# Vesta_cape_wifi.net
KiCad netlist of a schematic drawn in Altium Designer
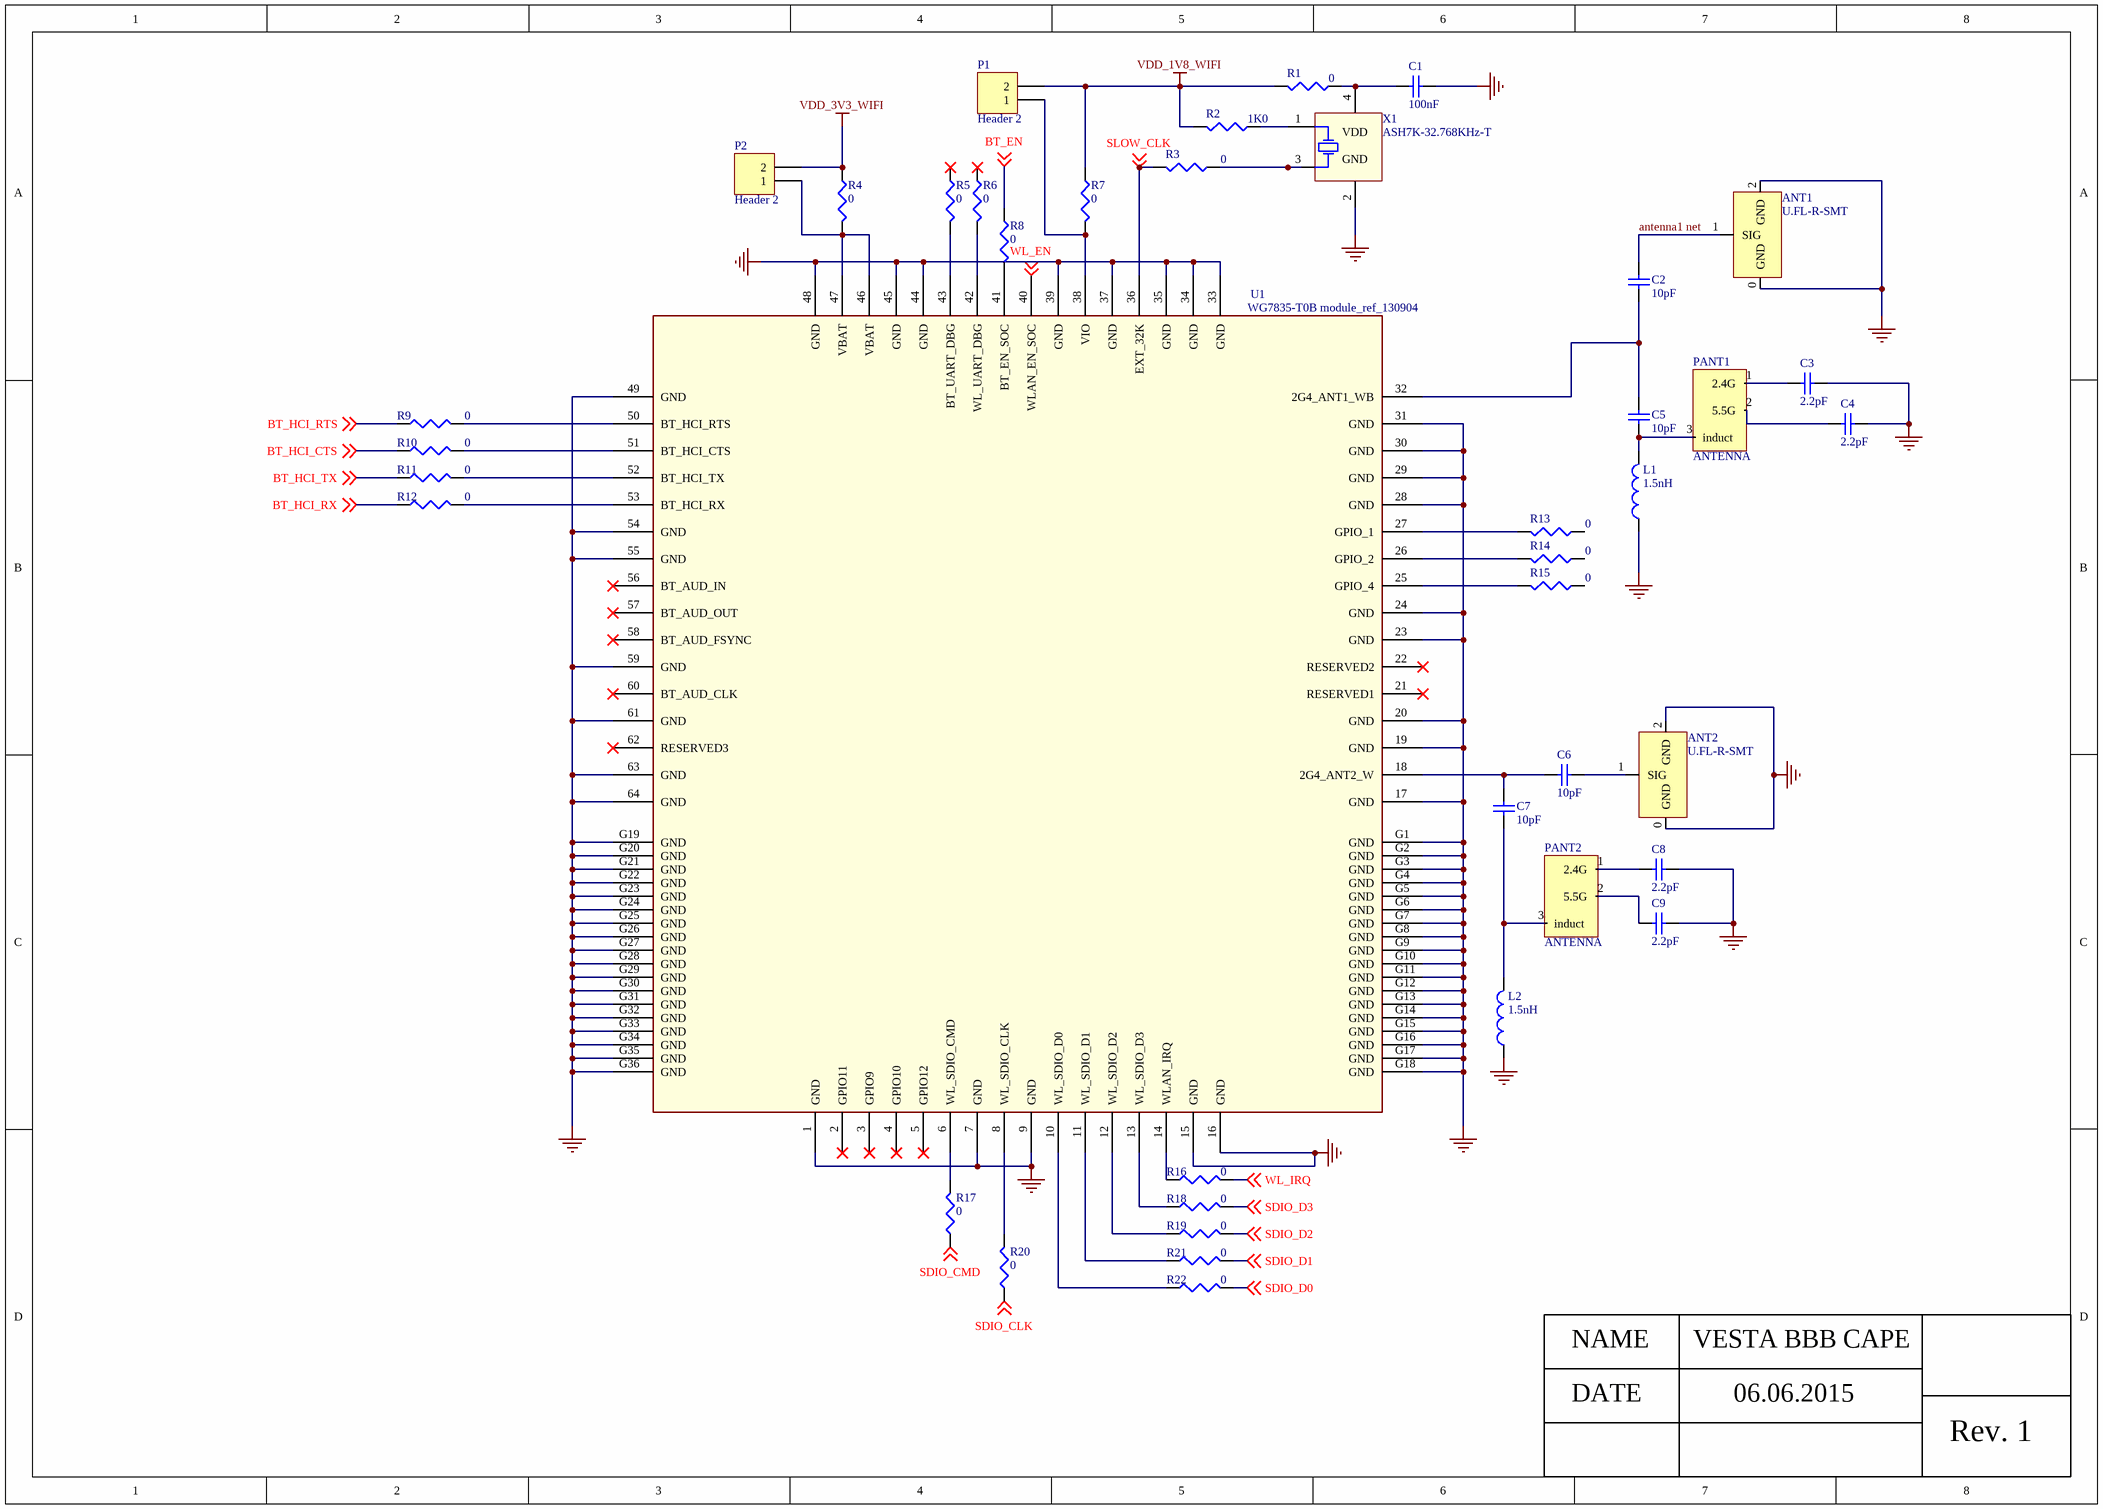
[diagram p0: Vesta_cape_wifi.SchDoc]

(export (version "E")
  (design (tool "Eeschema 10.0.6"))
  (components
    (comp (ref "ANT1")
      (value "U.FL-R-SMT")
      (footprint "U.FL-R-SMT")
      (libsource (lib "Vesta_cape") (part "U.FL-R-SMT"))
    )
    (comp (ref "ANT2")
      (value "U.FL-R-SMT")
      (footprint "U.FL-R-SMT")
      (libsource (lib "Vesta_cape") (part "U.FL-R-SMT"))
    )
    (comp (ref "C1")
      (value "100nF")
      (footprint "C1206")
      (description "Capacitor (Semiconductor SIM Model)")
      (fields (field (name "PUBLISHER") "Altium Limited"))
      (libsource (lib "Miscellaneous Devices") (part "Cap Semi"))
    )
    (comp (ref "C2")
      (value "10pF")
      (footprint "Capacitor_0603")
      (description "Capacitor (Semiconductor SIM Model)")
      (fields (field (name "PUBLISHER") "Altium Limited"))
      (libsource (lib "Miscellaneous Devices") (part "Cap Semi"))
    )
    (comp (ref "C3")
      (value "2.2pF")
      (footprint "Capacitor_0603")
      (description "Capacitor (Semiconductor SIM Model)")
      (fields (field (name "PUBLISHER") "Altium Limited"))
      (libsource (lib "Miscellaneous Devices") (part "Cap Semi"))
    )
    (comp (ref "C4")
      (value "2.2pF")
      (footprint "Capacitor_0603")
      (description "Capacitor (Semiconductor SIM Model)")
      (fields (field (name "PUBLISHER") "Altium Limited"))
      (libsource (lib "Miscellaneous Devices") (part "Cap Semi"))
    )
    (comp (ref "C5")
      (value "10pF")
      (footprint "Capacitor_0603")
      (description "Capacitor (Semiconductor SIM Model)")
      (fields (field (name "PUBLISHER") "Altium Limited"))
      (libsource (lib "Miscellaneous Devices") (part "Cap Semi"))
    )
    (comp (ref "C6")
      (value "10pF")
      (footprint "Capacitor_0603")
      (description "Capacitor (Semiconductor SIM Model)")
      (fields (field (name "PUBLISHER") "Altium Limited"))
      (libsource (lib "Miscellaneous Devices") (part "Cap Semi"))
    )
    (comp (ref "C7")
      (value "10pF")
      (footprint "Capacitor_0603")
      (description "Capacitor (Semiconductor SIM Model)")
      (fields (field (name "PUBLISHER") "Altium Limited"))
      (libsource (lib "Miscellaneous Devices") (part "Cap Semi"))
    )
    (comp (ref "C8")
      (value "2.2pF")
      (footprint "Capacitor_0603")
      (description "Capacitor (Semiconductor SIM Model)")
      (fields (field (name "PUBLISHER") "Altium Limited"))
      (libsource (lib "Miscellaneous Devices") (part "Cap Semi"))
    )
    (comp (ref "C9")
      (value "2.2pF")
      (footprint "Capacitor_0603")
      (description "Capacitor (Semiconductor SIM Model)")
      (fields (field (name "PUBLISHER") "Altium Limited"))
      (libsource (lib "Miscellaneous Devices") (part "Cap Semi"))
    )
    (comp (ref "L1")
      (value "1.5nH")
      (footprint "0402-A")
      (description "Inductor")
      (fields (field (name "PUBLISHER") "Altium Limited"))
      (libsource (lib "Miscellaneous Devices") (part "Inductor"))
    )
    (comp (ref "L2")
      (value "1.5nH")
      (footprint "0402-A")
      (description "Inductor")
      (fields (field (name "PUBLISHER") "Altium Limited"))
      (libsource (lib "Miscellaneous Devices") (part "Inductor"))
    )
    (comp (ref "P1")
      (value "Header 2")
      (footprint "HDR1X2")
      (description "Header, 2-Pin")
      (fields (field (name "PUBLISHER") "Altium Limited"))
      (libsource (lib "Miscellaneous Connectors") (part "Header 2"))
    )
    (comp (ref "P2")
      (value "Header 2")
      (footprint "HDR1X2")
      (description "Header, 2-Pin")
      (fields (field (name "PUBLISHER") "Altium Limited"))
      (libsource (lib "Miscellaneous Connectors") (part "Header 2"))
    )
    (comp (ref "PANT1")
      (value "ANTENNA")
      (footprint "ANT_BRD_CUT")
      (libsource (lib "Vesta_cape") (part "ANTENNA"))
    )
    (comp (ref "PANT2")
      (value "ANTENNA")
      (footprint "ANT_BRD_CUT")
      (libsource (lib "Vesta_cape") (part "ANTENNA"))
    )
    (comp (ref "R1")
      (value "0")
      (footprint "J1-0603")
      (description "Resistor")
      (fields (field (name "PUBLISHER") "Altium Limited"))
      (libsource (lib "Miscellaneous Devices") (part "Res3"))
    )
    (comp (ref "R2")
      (value "1K0")
      (footprint "J1-0603")
      (description "Resistor")
      (fields (field (name "PUBLISHER") "Altium Limited"))
      (libsource (lib "Miscellaneous Devices") (part "Res3"))
    )
    (comp (ref "R3")
      (value "0")
      (footprint "J1-0603")
      (description "Resistor")
      (fields (field (name "PUBLISHER") "Altium Limited"))
      (libsource (lib "Miscellaneous Devices") (part "Res3"))
    )
    (comp (ref "R4")
      (value "0")
      (footprint "J1-0603")
      (description "Resistor")
      (fields (field (name "PUBLISHER") "Altium Limited"))
      (libsource (lib "Miscellaneous Devices") (part "Res3"))
    )
    (comp (ref "R5")
      (value "0")
      (footprint "J1-0603")
      (description "Resistor")
      (fields (field (name "PUBLISHER") "Altium Limited"))
      (libsource (lib "Miscellaneous Devices") (part "Res3"))
    )
    (comp (ref "R6")
      (value "0")
      (footprint "J1-0603")
      (description "Resistor")
      (fields (field (name "PUBLISHER") "Altium Limited"))
      (libsource (lib "Miscellaneous Devices") (part "Res3"))
    )
    (comp (ref "R7")
      (value "0")
      (footprint "J1-0603")
      (description "Resistor")
      (fields (field (name "PUBLISHER") "Altium Limited"))
      (libsource (lib "Miscellaneous Devices") (part "Res3"))
    )
    (comp (ref "R8")
      (value "0")
      (footprint "J1-0603")
      (description "Resistor")
      (fields (field (name "PUBLISHER") "Altium Limited"))
      (libsource (lib "Miscellaneous Devices") (part "Res3"))
    )
    (comp (ref "R9")
      (value "0")
      (footprint "J1-0603")
      (description "Resistor")
      (fields (field (name "PUBLISHER") "Altium Limited"))
      (libsource (lib "Miscellaneous Devices") (part "Res3"))
    )
    (comp (ref "R10")
      (value "0")
      (footprint "J1-0603")
      (description "Resistor")
      (fields (field (name "PUBLISHER") "Altium Limited"))
      (libsource (lib "Miscellaneous Devices") (part "Res3"))
    )
    (comp (ref "R11")
      (value "0")
      (footprint "J1-0603")
      (description "Resistor")
      (fields (field (name "PUBLISHER") "Altium Limited"))
      (libsource (lib "Miscellaneous Devices") (part "Res3"))
    )
    (comp (ref "R12")
      (value "0")
      (footprint "J1-0603")
      (description "Resistor")
      (fields (field (name "PUBLISHER") "Altium Limited"))
      (libsource (lib "Miscellaneous Devices") (part "Res3"))
    )
    (comp (ref "R13")
      (value "0")
      (footprint "J1-0603")
      (description "Resistor")
      (fields (field (name "PUBLISHER") "Altium Limited"))
      (libsource (lib "Miscellaneous Devices") (part "Res3"))
    )
    (comp (ref "R14")
      (value "0")
      (footprint "J1-0603")
      (description "Resistor")
      (fields (field (name "PUBLISHER") "Altium Limited"))
      (libsource (lib "Miscellaneous Devices") (part "Res3"))
    )
    (comp (ref "R15")
      (value "0")
      (footprint "J1-0603")
      (description "Resistor")
      (fields (field (name "PUBLISHER") "Altium Limited"))
      (libsource (lib "Miscellaneous Devices") (part "Res3"))
    )
    (comp (ref "R16")
      (value "0")
      (footprint "J1-0603")
      (description "Resistor")
      (fields (field (name "PUBLISHER") "Altium Limited"))
      (libsource (lib "Miscellaneous Devices") (part "Res3"))
    )
    (comp (ref "R17")
      (value "0")
      (footprint "J1-0603")
      (description "Resistor")
      (fields (field (name "PUBLISHER") "Altium Limited"))
      (libsource (lib "Miscellaneous Devices") (part "Res3"))
    )
    (comp (ref "R18")
      (value "0")
      (footprint "J1-0603")
      (description "Resistor")
      (fields (field (name "PUBLISHER") "Altium Limited"))
      (libsource (lib "Miscellaneous Devices") (part "Res3"))
    )
    (comp (ref "R19")
      (value "0")
      (footprint "J1-0603")
      (description "Resistor")
      (fields (field (name "PUBLISHER") "Altium Limited"))
      (libsource (lib "Miscellaneous Devices") (part "Res3"))
    )
    (comp (ref "R20")
      (value "0")
      (footprint "J1-0603")
      (description "Resistor")
      (fields (field (name "PUBLISHER") "Altium Limited"))
      (libsource (lib "Miscellaneous Devices") (part "Res3"))
    )
    (comp (ref "R21")
      (value "0")
      (footprint "J1-0603")
      (description "Resistor")
      (fields (field (name "PUBLISHER") "Altium Limited"))
      (libsource (lib "Miscellaneous Devices") (part "Res3"))
    )
    (comp (ref "R22")
      (value "0")
      (footprint "J1-0603")
      (description "Resistor")
      (fields (field (name "PUBLISHER") "Altium Limited"))
      (libsource (lib "Miscellaneous Devices") (part "Res3"))
    )
    (comp (ref "U1")
      (value "WG7835-T0B module_ref_130904")
      (footprint "E-13.4X13.3-N100_0.75-TOP")
      (libsource (lib "WL1835MODCOM8B_Library") (part "WG7835-T0B module_ref_130904"))
    )
    (comp (ref "X1")
      (value "ASH7K-32.768KHz-T")
      (footprint "ABRA-ASH7K-4_V")
      (description "Crystal Oscillator, 32.768 kHz, -40 to 80 degC, 3.2 x 1.5 x 1.0 mm SMD, Tape and Reel")
      (fields (field (name "MANUFACTURER") "Abracon"))
      (libsource (lib "Altium Content Vault") (part "CMP-0448-00001-2"))
    )
  )
  (nets
    (net (code "1") (name "/antenna1 net") (class "Default")
      (node (ref "ANT1") (pin "1") (pinfunction "SIG_1") (pintype "passive"))
      (node (ref "C2") (pin "2") (pinfunction "2_2") (pintype "passive"))
    )
    (net (code "2") (name "BT_EN") (class "Default")
      (node (ref "R8") (pin "1") (pinfunction "1_1") (pintype "passive"))
    )
    (net (code "3") (name "BT_HCI_CTS") (class "Default")
      (node (ref "R10") (pin "1") (pinfunction "1_1") (pintype "passive"))
    )
    (net (code "4") (name "BT_HCI_RTS") (class "Default")
      (node (ref "R9") (pin "1") (pinfunction "1_1") (pintype "passive"))
    )
    (net (code "5") (name "BT_HCI_RX") (class "Default")
      (node (ref "R12") (pin "1") (pinfunction "1_1") (pintype "passive"))
    )
    (net (code "6") (name "BT_HCI_TX") (class "Default")
      (node (ref "R11") (pin "1") (pinfunction "1_1") (pintype "passive"))
    )
    (net (code "7") (name "GND") (class "Default")
      (node (ref "ANT1") (pin "0") (pinfunction "GND_0") (pintype "passive"))
      (node (ref "ANT1") (pin "2") (pinfunction "GND_2") (pintype "passive"))
      (node (ref "ANT2") (pin "0") (pinfunction "GND_0") (pintype "passive"))
      (node (ref "ANT2") (pin "2") (pinfunction "GND_2") (pintype "passive"))
      (node (ref "C1") (pin "1") (pinfunction "1_1") (pintype "passive"))
      (node (ref "C3") (pin "2") (pinfunction "2_2") (pintype "passive"))
      (node (ref "C4") (pin "2") (pinfunction "2_2") (pintype "passive"))
      (node (ref "C8") (pin "2") (pinfunction "2_2") (pintype "passive"))
      (node (ref "C9") (pin "2") (pinfunction "2_2") (pintype "passive"))
      (node (ref "L1") (pin "1") (pinfunction "1_1") (pintype "passive"))
      (node (ref "L2") (pin "1") (pinfunction "1_1") (pintype "passive"))
      (node (ref "U1") (pin "1") (pinfunction "GND_1") (pintype "power_in"))
      (node (ref "U1") (pin "15") (pinfunction "GND_15") (pintype "power_in"))
      (node (ref "U1") (pin "16") (pinfunction "GND_16") (pintype "power_in"))
      (node (ref "U1") (pin "17") (pinfunction "GND_17") (pintype "power_in"))
      (node (ref "U1") (pin "19") (pinfunction "GND_19") (pintype "power_in"))
      (node (ref "U1") (pin "20") (pinfunction "GND_20") (pintype "power_in"))
      (node (ref "U1") (pin "23") (pinfunction "GND_23") (pintype "power_in"))
      (node (ref "U1") (pin "24") (pinfunction "GND_24") (pintype "power_in"))
      (node (ref "U1") (pin "28") (pinfunction "GND_28") (pintype "power_in"))
      (node (ref "U1") (pin "29") (pinfunction "GND_29") (pintype "power_in"))
      (node (ref "U1") (pin "30") (pinfunction "GND_30") (pintype "power_in"))
      (node (ref "U1") (pin "31") (pinfunction "GND_31") (pintype "power_in"))
      (node (ref "U1") (pin "33") (pinfunction "GND_33") (pintype "power_in"))
      (node (ref "U1") (pin "34") (pinfunction "GND_34") (pintype "power_in"))
      (node (ref "U1") (pin "35") (pinfunction "GND_35") (pintype "power_in"))
      (node (ref "U1") (pin "37") (pinfunction "GND_37") (pintype "power_in"))
      (node (ref "U1") (pin "39") (pinfunction "GND_39") (pintype "power_in"))
      (node (ref "U1") (pin "44") (pinfunction "GND_44") (pintype "power_in"))
      (node (ref "U1") (pin "45") (pinfunction "GND_45") (pintype "power_in"))
      (node (ref "U1") (pin "48") (pinfunction "GND_48") (pintype "power_in"))
      (node (ref "U1") (pin "49") (pinfunction "GND_49") (pintype "power_in"))
      (node (ref "U1") (pin "54") (pinfunction "GND_54") (pintype "power_in"))
      (node (ref "U1") (pin "55") (pinfunction "GND_55") (pintype "power_in"))
      (node (ref "U1") (pin "59") (pinfunction "GND_59") (pintype "power_in"))
      (node (ref "U1") (pin "61") (pinfunction "GND_61") (pintype "power_in"))
      (node (ref "U1") (pin "63") (pinfunction "GND_63") (pintype "power_in"))
      (node (ref "U1") (pin "64") (pinfunction "GND_64") (pintype "power_in"))
      (node (ref "U1") (pin "7") (pinfunction "GND_7") (pintype "power_in"))
      (node (ref "U1") (pin "9") (pinfunction "GND_9") (pintype "power_in"))
      (node (ref "U1") (pin "G1") (pinfunction "GND_G1") (pintype "power_in"))
      (node (ref "U1") (pin "G10") (pinfunction "GND_G10") (pintype "power_in"))
      (node (ref "U1") (pin "G11") (pinfunction "GND_G11") (pintype "power_in"))
      (node (ref "U1") (pin "G12") (pinfunction "GND_G12") (pintype "power_in"))
      (node (ref "U1") (pin "G13") (pinfunction "GND_G13") (pintype "power_in"))
      (node (ref "U1") (pin "G14") (pinfunction "GND_G14") (pintype "power_in"))
      (node (ref "U1") (pin "G15") (pinfunction "GND_G15") (pintype "power_in"))
      (node (ref "U1") (pin "G16") (pinfunction "GND_G16") (pintype "power_in"))
      (node (ref "U1") (pin "G17") (pinfunction "GND_G17") (pintype "power_in"))
      (node (ref "U1") (pin "G18") (pinfunction "GND_G18") (pintype "power_in"))
      (node (ref "U1") (pin "G19") (pinfunction "GND_G19") (pintype "power_in"))
      (node (ref "U1") (pin "G2") (pinfunction "GND_G2") (pintype "power_in"))
      (node (ref "U1") (pin "G20") (pinfunction "GND_G20") (pintype "power_in"))
      (node (ref "U1") (pin "G21") (pinfunction "GND_G21") (pintype "power_in"))
      (node (ref "U1") (pin "G22") (pinfunction "GND_G22") (pintype "power_in"))
      (node (ref "U1") (pin "G23") (pinfunction "GND_G23") (pintype "power_in"))
      (node (ref "U1") (pin "G24") (pinfunction "GND_G24") (pintype "power_in"))
      (node (ref "U1") (pin "G25") (pinfunction "GND_G25") (pintype "power_in"))
      (node (ref "U1") (pin "G26") (pinfunction "GND_G26") (pintype "power_in"))
      (node (ref "U1") (pin "G27") (pinfunction "GND_G27") (pintype "power_in"))
      (node (ref "U1") (pin "G28") (pinfunction "GND_G28") (pintype "power_in"))
      (node (ref "U1") (pin "G29") (pinfunction "GND_G29") (pintype "power_in"))
      (node (ref "U1") (pin "G3") (pinfunction "GND_G3") (pintype "power_in"))
      (node (ref "U1") (pin "G30") (pinfunction "GND_G30") (pintype "power_in"))
      (node (ref "U1") (pin "G31") (pinfunction "GND_G31") (pintype "power_in"))
      (node (ref "U1") (pin "G32") (pinfunction "GND_G32") (pintype "power_in"))
      (node (ref "U1") (pin "G33") (pinfunction "GND_G33") (pintype "power_in"))
      (node (ref "U1") (pin "G34") (pinfunction "GND_G34") (pintype "power_in"))
      (node (ref "U1") (pin "G35") (pinfunction "GND_G35") (pintype "power_in"))
      (node (ref "U1") (pin "G36") (pinfunction "GND_G36") (pintype "power_in"))
      (node (ref "U1") (pin "G4") (pinfunction "GND_G4") (pintype "power_in"))
      (node (ref "U1") (pin "G5") (pinfunction "GND_G5") (pintype "power_in"))
      (node (ref "U1") (pin "G6") (pinfunction "GND_G6") (pintype "power_in"))
      (node (ref "U1") (pin "G7") (pinfunction "GND_G7") (pintype "power_in"))
      (node (ref "U1") (pin "G8") (pinfunction "GND_G8") (pintype "power_in"))
      (node (ref "U1") (pin "G9") (pinfunction "GND_G9") (pintype "power_in"))
      (node (ref "X1") (pin "2") (pinfunction "GND_2") (pintype "power_in"))
    )
    (net (code "8") (name "Net-(ANT2-SIG)") (class "Default")
      (node (ref "ANT2") (pin "1") (pinfunction "SIG_1") (pintype "passive"))
      (node (ref "C6") (pin "2") (pinfunction "2_2") (pintype "passive"))
    )
    (net (code "9") (name "Net-(P2-Pad1)") (class "Default")
      (node (ref "P2") (pin "1") (pinfunction "1_1") (pintype "passive"))
      (node (ref "R4") (pin "2") (pinfunction "2_2") (pintype "passive"))
      (node (ref "U1") (pin "46") (pinfunction "VBAT_46") (pintype "power_in"))
      (node (ref "U1") (pin "47") (pinfunction "VBAT_47") (pintype "power_in"))
    )
    (net (code "10") (name "Net-(PANT1-2.4G)") (class "Default")
      (node (ref "C3") (pin "1") (pinfunction "1_1") (pintype "passive"))
      (node (ref "PANT1") (pin "1") (pinfunction "2.4G_1") (pintype "passive"))
    )
    (net (code "11") (name "Net-(PANT1-5.5G)") (class "Default")
      (node (ref "C4") (pin "1") (pinfunction "1_1") (pintype "passive"))
      (node (ref "PANT1") (pin "2") (pinfunction "5.5G_2") (pintype "passive"))
    )
    (net (code "12") (name "Net-(PANT1-induct)") (class "Default")
      (node (ref "C5") (pin "1") (pinfunction "1_1") (pintype "passive"))
      (node (ref "L1") (pin "2") (pinfunction "2_2") (pintype "passive"))
      (node (ref "PANT1") (pin "3") (pinfunction "induct_3") (pintype "passive"))
    )
    (net (code "13") (name "Net-(PANT2-2.4G)") (class "Default")
      (node (ref "C8") (pin "1") (pinfunction "1_1") (pintype "passive"))
      (node (ref "PANT2") (pin "1") (pinfunction "2.4G_1") (pintype "passive"))
    )
    (net (code "14") (name "Net-(PANT2-5.5G)") (class "Default")
      (node (ref "C9") (pin "1") (pinfunction "1_1") (pintype "passive"))
      (node (ref "PANT2") (pin "2") (pinfunction "5.5G_2") (pintype "passive"))
    )
    (net (code "15") (name "Net-(PANT2-induct)") (class "Default")
      (node (ref "C7") (pin "1") (pinfunction "1_1") (pintype "passive"))
      (node (ref "L2") (pin "2") (pinfunction "2_2") (pintype "passive"))
      (node (ref "PANT2") (pin "3") (pinfunction "induct_3") (pintype "passive"))
    )
    (net (code "16") (name "Net-(U1-2G4_ANT1_WB)") (class "Default")
      (node (ref "C2") (pin "1") (pinfunction "1_1") (pintype "passive"))
      (node (ref "C5") (pin "2") (pinfunction "2_2") (pintype "passive"))
      (node (ref "U1") (pin "32") (pinfunction "2G4_ANT1_WB_32") (pintype "passive"))
    )
    (net (code "17") (name "Net-(U1-2G4_ANT2_W)") (class "Default")
      (node (ref "C6") (pin "1") (pinfunction "1_1") (pintype "passive"))
      (node (ref "C7") (pin "2") (pinfunction "2_2") (pintype "passive"))
      (node (ref "U1") (pin "18") (pinfunction "2G4_ANT2_W_18") (pintype "passive"))
    )
    (net (code "18") (name "Net-(U1-BT_EN_SOC)") (class "Default")
      (node (ref "R8") (pin "2") (pinfunction "2_2") (pintype "passive"))
      (node (ref "U1") (pin "41") (pinfunction "BT_EN_SOC_41") (pintype "passive"))
    )
    (net (code "19") (name "Net-(U1-BT_HCI_CTS)") (class "Default")
      (node (ref "R10") (pin "2") (pinfunction "2_2") (pintype "passive"))
      (node (ref "U1") (pin "51") (pinfunction "BT_HCI_CTS_51") (pintype "passive"))
    )
    (net (code "20") (name "Net-(U1-BT_HCI_RTS)") (class "Default")
      (node (ref "R9") (pin "2") (pinfunction "2_2") (pintype "passive"))
      (node (ref "U1") (pin "50") (pinfunction "BT_HCI_RTS_50") (pintype "passive"))
    )
    (net (code "21") (name "Net-(U1-BT_HCI_RX)") (class "Default")
      (node (ref "R12") (pin "2") (pinfunction "2_2") (pintype "passive"))
      (node (ref "U1") (pin "53") (pinfunction "BT_HCI_RX_53") (pintype "passive"))
    )
    (net (code "22") (name "Net-(U1-BT_HCI_TX)") (class "Default")
      (node (ref "R11") (pin "2") (pinfunction "2_2") (pintype "passive"))
      (node (ref "U1") (pin "52") (pinfunction "BT_HCI_TX_52") (pintype "passive"))
    )
    (net (code "23") (name "Net-(U1-BT_UART_DBG)") (class "Default")
      (node (ref "R5") (pin "2") (pinfunction "2_2") (pintype "passive"))
      (node (ref "U1") (pin "43") (pinfunction "BT_UART_DBG_43") (pintype "passive"))
    )
    (net (code "24") (name "Net-(U1-GPIO_1)") (class "Default")
      (node (ref "R13") (pin "2") (pinfunction "2_2") (pintype "passive"))
      (node (ref "U1") (pin "27") (pinfunction "GPIO_1_27") (pintype "passive"))
    )
    (net (code "25") (name "Net-(U1-GPIO_2)") (class "Default")
      (node (ref "R14") (pin "2") (pinfunction "2_2") (pintype "passive"))
      (node (ref "U1") (pin "26") (pinfunction "GPIO_2_26") (pintype "passive"))
    )
    (net (code "26") (name "Net-(U1-GPIO_4)") (class "Default")
      (node (ref "R15") (pin "2") (pinfunction "2_2") (pintype "passive"))
      (node (ref "U1") (pin "25") (pinfunction "GPIO_4_25") (pintype "passive"))
    )
    (net (code "27") (name "Net-(U1-VIO)") (class "Default")
      (node (ref "P1") (pin "1") (pinfunction "1_1") (pintype "passive"))
      (node (ref "R7") (pin "2") (pinfunction "2_2") (pintype "passive"))
      (node (ref "U1") (pin "38") (pinfunction "VIO_38") (pintype "power_in"))
    )
    (net (code "28") (name "Net-(U1-WLAN_IRQ)") (class "Default")
      (node (ref "R16") (pin "1") (pinfunction "1_1") (pintype "passive"))
      (node (ref "U1") (pin "14") (pinfunction "WLAN_IRQ_14") (pintype "passive"))
    )
    (net (code "29") (name "Net-(U1-WL_SDIO_CLK)") (class "Default")
      (node (ref "R20") (pin "2") (pinfunction "2_2") (pintype "passive"))
      (node (ref "U1") (pin "8") (pinfunction "WL_SDIO_CLK_8") (pintype "passive"))
    )
    (net (code "30") (name "Net-(U1-WL_SDIO_CMD)") (class "Default")
      (node (ref "R17") (pin "2") (pinfunction "2_2") (pintype "passive"))
      (node (ref "U1") (pin "6") (pinfunction "WL_SDIO_CMD_6") (pintype "passive"))
    )
    (net (code "31") (name "Net-(U1-WL_SDIO_D0)") (class "Default")
      (node (ref "R22") (pin "1") (pinfunction "1_1") (pintype "passive"))
      (node (ref "U1") (pin "10") (pinfunction "WL_SDIO_D0_10") (pintype "passive"))
    )
    (net (code "32") (name "Net-(U1-WL_SDIO_D1)") (class "Default")
      (node (ref "R21") (pin "1") (pinfunction "1_1") (pintype "passive"))
      (node (ref "U1") (pin "11") (pinfunction "WL_SDIO_D1_11") (pintype "passive"))
    )
    (net (code "33") (name "Net-(U1-WL_SDIO_D2)") (class "Default")
      (node (ref "R19") (pin "1") (pinfunction "1_1") (pintype "passive"))
      (node (ref "U1") (pin "12") (pinfunction "WL_SDIO_D2_12") (pintype "passive"))
    )
    (net (code "34") (name "Net-(U1-WL_SDIO_D3)") (class "Default")
      (node (ref "R18") (pin "1") (pinfunction "1_1") (pintype "passive"))
      (node (ref "U1") (pin "13") (pinfunction "WL_SDIO_D3_13") (pintype "passive"))
    )
    (net (code "35") (name "Net-(U1-WL_UART_DBG)") (class "Default")
      (node (ref "R6") (pin "2") (pinfunction "2_2") (pintype "passive"))
      (node (ref "U1") (pin "42") (pinfunction "WL_UART_DBG_42") (pintype "passive"))
    )
    (net (code "36") (name "Net-(X1-Output)") (class "Default")
      (node (ref "R3") (pin "1") (pinfunction "1_1") (pintype "passive"))
      (node (ref "X1") (pin "3") (pinfunction "Output_3") (pintype "tri_state"))
    )
    (net (code "37") (name "Net-(X1-VDD)") (class "Default")
      (node (ref "C1") (pin "2") (pinfunction "2_2") (pintype "passive"))
      (node (ref "R1") (pin "1") (pinfunction "1_1") (pintype "passive"))
      (node (ref "X1") (pin "4") (pinfunction "VDD_4") (pintype "power_in"))
    )
    (net (code "38") (name "Net-(X1-VIO)") (class "Default")
      (node (ref "R2") (pin "1") (pinfunction "1_1") (pintype "passive"))
      (node (ref "X1") (pin "1") (pinfunction "VIO_1") (pintype "power_in"))
    )
    (net (code "39") (name "SDIO_CLK") (class "Default")
      (node (ref "R20") (pin "1") (pinfunction "1_1") (pintype "passive"))
    )
    (net (code "40") (name "SDIO_CMD") (class "Default")
      (node (ref "R17") (pin "1") (pinfunction "1_1") (pintype "passive"))
    )
    (net (code "41") (name "SDIO_D0") (class "Default")
      (node (ref "R22") (pin "2") (pinfunction "2_2") (pintype "passive"))
    )
    (net (code "42") (name "SDIO_D1") (class "Default")
      (node (ref "R21") (pin "2") (pinfunction "2_2") (pintype "passive"))
    )
    (net (code "43") (name "SDIO_D2") (class "Default")
      (node (ref "R19") (pin "2") (pinfunction "2_2") (pintype "passive"))
    )
    (net (code "44") (name "SDIO_D3") (class "Default")
      (node (ref "R18") (pin "2") (pinfunction "2_2") (pintype "passive"))
    )
    (net (code "45") (name "SLOW_CLK") (class "Default")
      (node (ref "R3") (pin "2") (pinfunction "2_2") (pintype "passive"))
      (node (ref "U1") (pin "36") (pinfunction "EXT_32K_36") (pintype "passive"))
    )
    (net (code "46") (name "VDD_1V8_WIFI") (class "Default")
      (node (ref "P1") (pin "2") (pinfunction "2_2") (pintype "passive"))
      (node (ref "R1") (pin "2") (pinfunction "2_2") (pintype "passive"))
      (node (ref "R2") (pin "2") (pinfunction "2_2") (pintype "passive"))
      (node (ref "R7") (pin "1") (pinfunction "1_1") (pintype "passive"))
    )
    (net (code "47") (name "VDD_3V3_WIFI") (class "Default")
      (node (ref "P2") (pin "2") (pinfunction "2_2") (pintype "passive"))
      (node (ref "R4") (pin "1") (pinfunction "1_1") (pintype "passive"))
    )
    (net (code "48") (name "WL_EN") (class "Default")
      (node (ref "U1") (pin "40") (pinfunction "WLAN_EN_SOC_40") (pintype "passive"))
    )
    (net (code "49") (name "WL_IRQ") (class "Default")
      (node (ref "R16") (pin "2") (pinfunction "2_2") (pintype "passive"))
    )
    (net (code "50") (name "unconnected-(R5-Pad1)") (class "Default")
      (node (ref "R5") (pin "1") (pinfunction "1_1") (pintype "passive+no_connect"))
    )
    (net (code "51") (name "unconnected-(R6-Pad1)") (class "Default")
      (node (ref "R6") (pin "1") (pinfunction "1_1") (pintype "passive+no_connect"))
    )
    (net (code "52") (name "unconnected-(R13-Pad1)") (class "Default")
      (node (ref "R13") (pin "1") (pinfunction "1_1") (pintype "passive"))
    )
    (net (code "53") (name "unconnected-(R14-Pad1)") (class "Default")
      (node (ref "R14") (pin "1") (pinfunction "1_1") (pintype "passive"))
    )
    (net (code "54") (name "unconnected-(R15-Pad1)") (class "Default")
      (node (ref "R15") (pin "1") (pinfunction "1_1") (pintype "passive"))
    )
    (net (code "55") (name "unconnected-(U1-BT_AUD_CLK-Pad60)") (class "Default")
      (node (ref "U1") (pin "60") (pinfunction "BT_AUD_CLK_60") (pintype "passive+no_connect"))
    )
    (net (code "56") (name "unconnected-(U1-BT_AUD_FSYNC-Pad58)") (class "Default")
      (node (ref "U1") (pin "58") (pinfunction "BT_AUD_FSYNC_58") (pintype "passive+no_connect"))
    )
    (net (code "57") (name "unconnected-(U1-BT_AUD_IN-Pad56)") (class "Default")
      (node (ref "U1") (pin "56") (pinfunction "BT_AUD_IN_56") (pintype "passive+no_connect"))
    )
    (net (code "58") (name "unconnected-(U1-BT_AUD_OUT-Pad57)") (class "Default")
      (node (ref "U1") (pin "57") (pinfunction "BT_AUD_OUT_57") (pintype "passive+no_connect"))
    )
    (net (code "59") (name "unconnected-(U1-GPIO9-Pad3)") (class "Default")
      (node (ref "U1") (pin "3") (pinfunction "GPIO9_3") (pintype "passive+no_connect"))
    )
    (net (code "60") (name "unconnected-(U1-GPIO10-Pad4)") (class "Default")
      (node (ref "U1") (pin "4") (pinfunction "GPIO10_4") (pintype "passive+no_connect"))
    )
    (net (code "61") (name "unconnected-(U1-GPIO11-Pad2)") (class "Default")
      (node (ref "U1") (pin "2") (pinfunction "GPIO11_2") (pintype "passive+no_connect"))
    )
    (net (code "62") (name "unconnected-(U1-GPIO12-Pad5)") (class "Default")
      (node (ref "U1") (pin "5") (pinfunction "GPIO12_5") (pintype "passive+no_connect"))
    )
    (net (code "63") (name "unconnected-(U1-RESERVED1-Pad21)") (class "Default")
      (node (ref "U1") (pin "21") (pinfunction "RESERVED1_21") (pintype "passive+no_connect"))
    )
    (net (code "64") (name "unconnected-(U1-RESERVED2-Pad22)") (class "Default")
      (node (ref "U1") (pin "22") (pinfunction "RESERVED2_22") (pintype "passive+no_connect"))
    )
    (net (code "65") (name "unconnected-(U1-RESERVED3-Pad62)") (class "Default")
      (node (ref "U1") (pin "62") (pinfunction "RESERVED3_62") (pintype "passive+no_connect"))
    )
  )
)
